# LFR_Array_v2_0.net
KiCad netlist of a schematic drawn in Altium Designer
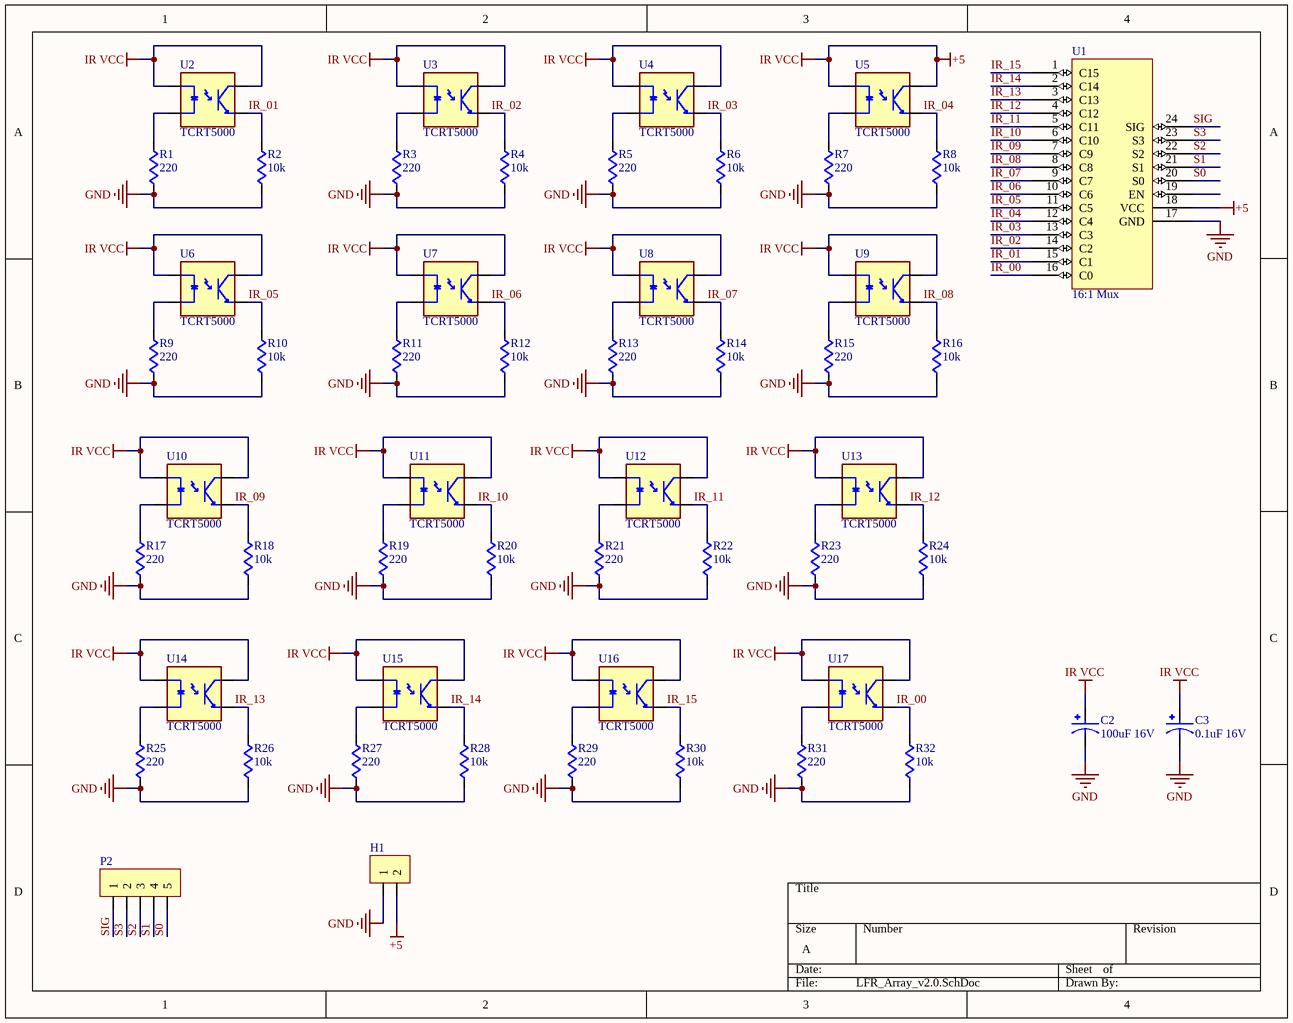
[diagram p0: LFR_Array_v2.0.SchDoc]

(export (version "E")
  (design (tool "Eeschema 10.0.6"))
  (components
    (comp (ref "C2")
      (value "100uF 16V")
      (footprint "100uF  16V")
      (description "CAP ALUM 100uF 16V RADIAL TH")
      (fields (field (name "MP") "EEU-FR1E221B") (field (name "MF") "Panasonic Electronic Components"))
      (libsource (lib "Capacitor TH") (part "100uF 16V"))
    )
    (comp (ref "C3")
      (value "0.1uF 16V")
      (footprint "0.1uF 16V")
      (description "Cap 0.1uF 16VRADIAL TH")
      (fields (field (name "MP") "EEU-FR1E221B") (field (name "MF") "Panasonic Electronic Components"))
      (libsource (lib "Capacitor TH") (part "0.1uF 16V"))
    )
    (comp (ref "H1")
      (value "Header 1x3")
      (footprint "Header 1x2 male CNC")
      (libsource (lib "Pin Header") (part "Header 1x2"))
    )
    (comp (ref "P2")
      (value "Header 1x5")
      (footprint "Header 1x5 male")
      (libsource (lib "Pin Header") (part "Header 1x5"))
    )
    (comp (ref "R1")
      (value "220")
      (footprint "1/4W resistor TH CNC")
      (description "Axial Resistor,reg 220 th")
      (fields (field (name "TOLERANCE") "1%"))
      (libsource (lib "Resistor Generic") (part "reg 220 th"))
    )
    (comp (ref "R2")
      (value "10k")
      (footprint "1/4W resistor TH CNC")
      (description "Axial Resistor,reg 10k th")
      (fields (field (name "TOLERANCE") "1%"))
      (libsource (lib "Resistor Generic") (part "reg 10k th"))
    )
    (comp (ref "R3")
      (value "220")
      (footprint "1/4W resistor TH CNC")
      (description "Axial Resistor,reg 220 th")
      (fields (field (name "TOLERANCE") "1%"))
      (libsource (lib "Resistor Generic") (part "reg 220 th"))
    )
    (comp (ref "R4")
      (value "10k")
      (footprint "1/4W resistor TH CNC")
      (description "Axial Resistor,reg 10k th")
      (fields (field (name "TOLERANCE") "1%"))
      (libsource (lib "Resistor Generic") (part "reg 10k th"))
    )
    (comp (ref "R5")
      (value "220")
      (footprint "1/4W resistor TH CNC")
      (description "Axial Resistor,reg 220 th")
      (fields (field (name "TOLERANCE") "1%"))
      (libsource (lib "Resistor Generic") (part "reg 220 th"))
    )
    (comp (ref "R6")
      (value "10k")
      (footprint "1/4W resistor TH CNC")
      (description "Axial Resistor,reg 10k th")
      (fields (field (name "TOLERANCE") "1%"))
      (libsource (lib "Resistor Generic") (part "reg 10k th"))
    )
    (comp (ref "R7")
      (value "220")
      (footprint "1/4W resistor TH CNC")
      (description "Axial Resistor,reg 220 th")
      (fields (field (name "TOLERANCE") "1%"))
      (libsource (lib "Resistor Generic") (part "reg 220 th"))
    )
    (comp (ref "R8")
      (value "10k")
      (footprint "1/4W resistor TH CNC")
      (description "Axial Resistor,reg 10k th")
      (fields (field (name "TOLERANCE") "1%"))
      (libsource (lib "Resistor Generic") (part "reg 10k th"))
    )
    (comp (ref "R9")
      (value "220")
      (footprint "1/4W resistor TH CNC")
      (description "Axial Resistor,reg 220 th")
      (fields (field (name "TOLERANCE") "1%"))
      (libsource (lib "Resistor Generic") (part "reg 220 th"))
    )
    (comp (ref "R10")
      (value "10k")
      (footprint "1/4W resistor TH CNC")
      (description "Axial Resistor,reg 10k th")
      (fields (field (name "TOLERANCE") "1%"))
      (libsource (lib "Resistor Generic") (part "reg 10k th"))
    )
    (comp (ref "R11")
      (value "220")
      (footprint "1/4W resistor TH CNC")
      (description "Axial Resistor,reg 220 th")
      (fields (field (name "TOLERANCE") "1%"))
      (libsource (lib "Resistor Generic") (part "reg 220 th"))
    )
    (comp (ref "R12")
      (value "10k")
      (footprint "1/4W resistor TH CNC")
      (description "Axial Resistor,reg 10k th")
      (fields (field (name "TOLERANCE") "1%"))
      (libsource (lib "Resistor Generic") (part "reg 10k th"))
    )
    (comp (ref "R13")
      (value "220")
      (footprint "1/4W resistor TH CNC")
      (description "Axial Resistor,reg 220 th")
      (fields (field (name "TOLERANCE") "1%"))
      (libsource (lib "Resistor Generic") (part "reg 220 th"))
    )
    (comp (ref "R14")
      (value "10k")
      (footprint "1/4W resistor TH CNC")
      (description "Axial Resistor,reg 10k th")
      (fields (field (name "TOLERANCE") "1%"))
      (libsource (lib "Resistor Generic") (part "reg 10k th"))
    )
    (comp (ref "R15")
      (value "220")
      (footprint "1/4W resistor TH CNC")
      (description "Axial Resistor,reg 220 th")
      (fields (field (name "TOLERANCE") "1%"))
      (libsource (lib "Resistor Generic") (part "reg 220 th"))
    )
    (comp (ref "R16")
      (value "10k")
      (footprint "1/4W resistor TH CNC")
      (description "Axial Resistor,reg 10k th")
      (fields (field (name "TOLERANCE") "1%"))
      (libsource (lib "Resistor Generic") (part "reg 10k th"))
    )
    (comp (ref "R17")
      (value "220")
      (footprint "1/4W resistor TH CNC")
      (description "Axial Resistor,reg 220 th")
      (fields (field (name "TOLERANCE") "1%"))
      (libsource (lib "Resistor Generic") (part "reg 220 th"))
    )
    (comp (ref "R18")
      (value "10k")
      (footprint "1/4W resistor TH CNC")
      (description "Axial Resistor,reg 10k th")
      (fields (field (name "TOLERANCE") "1%"))
      (libsource (lib "Resistor Generic") (part "reg 10k th"))
    )
    (comp (ref "R19")
      (value "220")
      (footprint "1/4W resistor TH CNC")
      (description "Axial Resistor,reg 220 th")
      (fields (field (name "TOLERANCE") "1%"))
      (libsource (lib "Resistor Generic") (part "reg 220 th"))
    )
    (comp (ref "R20")
      (value "10k")
      (footprint "1/4W resistor TH CNC")
      (description "Axial Resistor,reg 10k th")
      (fields (field (name "TOLERANCE") "1%"))
      (libsource (lib "Resistor Generic") (part "reg 10k th"))
    )
    (comp (ref "R21")
      (value "220")
      (footprint "1/4W resistor TH CNC")
      (description "Axial Resistor,reg 220 th")
      (fields (field (name "TOLERANCE") "1%"))
      (libsource (lib "Resistor Generic") (part "reg 220 th"))
    )
    (comp (ref "R22")
      (value "10k")
      (footprint "1/4W resistor TH CNC")
      (description "Axial Resistor,reg 10k th")
      (fields (field (name "TOLERANCE") "1%"))
      (libsource (lib "Resistor Generic") (part "reg 10k th"))
    )
    (comp (ref "R23")
      (value "220")
      (footprint "1/4W resistor TH CNC")
      (description "Axial Resistor,reg 220 th")
      (fields (field (name "TOLERANCE") "1%"))
      (libsource (lib "Resistor Generic") (part "reg 220 th"))
    )
    (comp (ref "R24")
      (value "10k")
      (footprint "1/4W resistor TH CNC")
      (description "Axial Resistor,reg 10k th")
      (fields (field (name "TOLERANCE") "1%"))
      (libsource (lib "Resistor Generic") (part "reg 10k th"))
    )
    (comp (ref "R25")
      (value "220")
      (footprint "1/4W resistor TH CNC")
      (description "Axial Resistor,reg 220 th")
      (fields (field (name "TOLERANCE") "1%"))
      (libsource (lib "Resistor Generic") (part "reg 220 th"))
    )
    (comp (ref "R26")
      (value "10k")
      (footprint "1/4W resistor TH CNC")
      (description "Axial Resistor,reg 10k th")
      (fields (field (name "TOLERANCE") "1%"))
      (libsource (lib "Resistor Generic") (part "reg 10k th"))
    )
    (comp (ref "R27")
      (value "220")
      (footprint "1/4W resistor TH CNC")
      (description "Axial Resistor,reg 220 th")
      (fields (field (name "TOLERANCE") "1%"))
      (libsource (lib "Resistor Generic") (part "reg 220 th"))
    )
    (comp (ref "R28")
      (value "10k")
      (footprint "1/4W resistor TH CNC")
      (description "Axial Resistor,reg 10k th")
      (fields (field (name "TOLERANCE") "1%"))
      (libsource (lib "Resistor Generic") (part "reg 10k th"))
    )
    (comp (ref "R29")
      (value "220")
      (footprint "1/4W resistor TH CNC")
      (description "Axial Resistor,reg 220 th")
      (fields (field (name "TOLERANCE") "1%"))
      (libsource (lib "Resistor Generic") (part "reg 220 th"))
    )
    (comp (ref "R30")
      (value "10k")
      (footprint "1/4W resistor TH CNC")
      (description "Axial Resistor,reg 10k th")
      (fields (field (name "TOLERANCE") "1%"))
      (libsource (lib "Resistor Generic") (part "reg 10k th"))
    )
    (comp (ref "R31")
      (value "220")
      (footprint "1/4W resistor TH CNC")
      (description "Axial Resistor,reg 220 th")
      (fields (field (name "TOLERANCE") "1%"))
      (libsource (lib "Resistor Generic") (part "reg 220 th"))
    )
    (comp (ref "R32")
      (value "10k")
      (footprint "1/4W resistor TH CNC")
      (description "Axial Resistor,reg 10k th")
      (fields (field (name "TOLERANCE") "1%"))
      (libsource (lib "Resistor Generic") (part "reg 10k th"))
    )
    (comp (ref "U1")
      (value "16:1 Mux")
      (footprint "Mux 16Ch 74HC4067 Module")
      (libsource (lib "Mux 16Ch 74HC4067 Module") (part "Mux 16Ch 74HC4067 Module"))
    )
    (comp (ref "U2")
      (value "TCRT5000")
      (footprint "OPTO_TCRT5000")
      (description "950 nm 60 mA Through Hole Reflective Optical Sensor with Transistor Output")
      (libsource (lib "TCRT5000") (part "TCRT5000"))
    )
    (comp (ref "U3")
      (value "TCRT5000")
      (footprint "OPTO_TCRT5000")
      (description "950 nm 60 mA Through Hole Reflective Optical Sensor with Transistor Output")
      (libsource (lib "TCRT5000") (part "TCRT5000"))
    )
    (comp (ref "U4")
      (value "TCRT5000")
      (footprint "OPTO_TCRT5000")
      (description "950 nm 60 mA Through Hole Reflective Optical Sensor with Transistor Output")
      (libsource (lib "TCRT5000") (part "TCRT5000"))
    )
    (comp (ref "U5")
      (value "TCRT5000")
      (footprint "OPTO_TCRT5000")
      (description "950 nm 60 mA Through Hole Reflective Optical Sensor with Transistor Output")
      (libsource (lib "TCRT5000") (part "TCRT5000"))
    )
    (comp (ref "U6")
      (value "TCRT5000")
      (footprint "OPTO_TCRT5000")
      (description "950 nm 60 mA Through Hole Reflective Optical Sensor with Transistor Output")
      (libsource (lib "TCRT5000") (part "TCRT5000"))
    )
    (comp (ref "U7")
      (value "TCRT5000")
      (footprint "OPTO_TCRT5000")
      (description "950 nm 60 mA Through Hole Reflective Optical Sensor with Transistor Output")
      (libsource (lib "TCRT5000") (part "TCRT5000"))
    )
    (comp (ref "U8")
      (value "TCRT5000")
      (footprint "OPTO_TCRT5000")
      (description "950 nm 60 mA Through Hole Reflective Optical Sensor with Transistor Output")
      (libsource (lib "TCRT5000") (part "TCRT5000"))
    )
    (comp (ref "U9")
      (value "TCRT5000")
      (footprint "OPTO_TCRT5000")
      (description "950 nm 60 mA Through Hole Reflective Optical Sensor with Transistor Output")
      (libsource (lib "TCRT5000") (part "TCRT5000"))
    )
    (comp (ref "U10")
      (value "TCRT5000")
      (footprint "OPTO_TCRT5000")
      (description "950 nm 60 mA Through Hole Reflective Optical Sensor with Transistor Output")
      (libsource (lib "TCRT5000") (part "TCRT5000"))
    )
    (comp (ref "U11")
      (value "TCRT5000")
      (footprint "OPTO_TCRT5000")
      (description "950 nm 60 mA Through Hole Reflective Optical Sensor with Transistor Output")
      (libsource (lib "TCRT5000") (part "TCRT5000"))
    )
    (comp (ref "U12")
      (value "TCRT5000")
      (footprint "OPTO_TCRT5000")
      (description "950 nm 60 mA Through Hole Reflective Optical Sensor with Transistor Output")
      (libsource (lib "TCRT5000") (part "TCRT5000"))
    )
    (comp (ref "U13")
      (value "TCRT5000")
      (footprint "OPTO_TCRT5000")
      (description "950 nm 60 mA Through Hole Reflective Optical Sensor with Transistor Output")
      (libsource (lib "TCRT5000") (part "TCRT5000"))
    )
    (comp (ref "U14")
      (value "TCRT5000")
      (footprint "OPTO_TCRT5000")
      (description "950 nm 60 mA Through Hole Reflective Optical Sensor with Transistor Output")
      (libsource (lib "TCRT5000") (part "TCRT5000"))
    )
    (comp (ref "U15")
      (value "TCRT5000")
      (footprint "OPTO_TCRT5000")
      (description "950 nm 60 mA Through Hole Reflective Optical Sensor with Transistor Output")
      (libsource (lib "TCRT5000") (part "TCRT5000"))
    )
    (comp (ref "U16")
      (value "TCRT5000")
      (footprint "OPTO_TCRT5000")
      (description "950 nm 60 mA Through Hole Reflective Optical Sensor with Transistor Output")
      (libsource (lib "TCRT5000") (part "TCRT5000"))
    )
    (comp (ref "U17")
      (value "TCRT5000")
      (footprint "OPTO_TCRT5000")
      (description "950 nm 60 mA Through Hole Reflective Optical Sensor with Transistor Output")
      (libsource (lib "TCRT5000") (part "TCRT5000"))
    )
  )
  (nets
    (net (code "1") (name "+5") (class "Default")
      (node (ref "C2") (pin "P") (pinfunction "P_P") (pintype "passive"))
      (node (ref "C3") (pin "P") (pinfunction "P_P") (pintype "passive"))
      (node (ref "H1") (pin "2") (pinfunction "2_2") (pintype "passive"))
      (node (ref "U1") (pin "18") (pinfunction "VCC_18") (pintype "power_in"))
      (node (ref "U10") (pin "A") (pinfunction "A_A") (pintype "passive"))
      (node (ref "U10") (pin "COLL") (pinfunction "COLL_COLL") (pintype "passive"))
      (node (ref "U11") (pin "A") (pinfunction "A_A") (pintype "passive"))
      (node (ref "U11") (pin "COLL") (pinfunction "COLL_COLL") (pintype "passive"))
      (node (ref "U12") (pin "A") (pinfunction "A_A") (pintype "passive"))
      (node (ref "U12") (pin "COLL") (pinfunction "COLL_COLL") (pintype "passive"))
      (node (ref "U13") (pin "A") (pinfunction "A_A") (pintype "passive"))
      (node (ref "U13") (pin "COLL") (pinfunction "COLL_COLL") (pintype "passive"))
      (node (ref "U14") (pin "A") (pinfunction "A_A") (pintype "passive"))
      (node (ref "U14") (pin "COLL") (pinfunction "COLL_COLL") (pintype "passive"))
      (node (ref "U15") (pin "A") (pinfunction "A_A") (pintype "passive"))
      (node (ref "U15") (pin "COLL") (pinfunction "COLL_COLL") (pintype "passive"))
      (node (ref "U16") (pin "A") (pinfunction "A_A") (pintype "passive"))
      (node (ref "U16") (pin "COLL") (pinfunction "COLL_COLL") (pintype "passive"))
      (node (ref "U17") (pin "A") (pinfunction "A_A") (pintype "passive"))
      (node (ref "U17") (pin "COLL") (pinfunction "COLL_COLL") (pintype "passive"))
      (node (ref "U2") (pin "A") (pinfunction "A_A") (pintype "passive"))
      (node (ref "U2") (pin "COLL") (pinfunction "COLL_COLL") (pintype "passive"))
      (node (ref "U3") (pin "A") (pinfunction "A_A") (pintype "passive"))
      (node (ref "U3") (pin "COLL") (pinfunction "COLL_COLL") (pintype "passive"))
      (node (ref "U4") (pin "A") (pinfunction "A_A") (pintype "passive"))
      (node (ref "U4") (pin "COLL") (pinfunction "COLL_COLL") (pintype "passive"))
      (node (ref "U5") (pin "A") (pinfunction "A_A") (pintype "passive"))
      (node (ref "U5") (pin "COLL") (pinfunction "COLL_COLL") (pintype "passive"))
      (node (ref "U6") (pin "A") (pinfunction "A_A") (pintype "passive"))
      (node (ref "U6") (pin "COLL") (pinfunction "COLL_COLL") (pintype "passive"))
      (node (ref "U7") (pin "A") (pinfunction "A_A") (pintype "passive"))
      (node (ref "U7") (pin "COLL") (pinfunction "COLL_COLL") (pintype "passive"))
      (node (ref "U8") (pin "A") (pinfunction "A_A") (pintype "passive"))
      (node (ref "U8") (pin "COLL") (pinfunction "COLL_COLL") (pintype "passive"))
      (node (ref "U9") (pin "A") (pinfunction "A_A") (pintype "passive"))
      (node (ref "U9") (pin "COLL") (pinfunction "COLL_COLL") (pintype "passive"))
    )
    (net (code "2") (name "/IR_00") (class "Default")
      (node (ref "R32") (pin "2") (pinfunction "2_2") (pintype "passive"))
      (node (ref "U1") (pin "16") (pinfunction "C0_16") (pintype "bidirectional"))
      (node (ref "U17") (pin "E") (pinfunction "E_E") (pintype "passive"))
    )
    (net (code "3") (name "/IR_01") (class "Default")
      (node (ref "R2") (pin "2") (pinfunction "2_2") (pintype "passive"))
      (node (ref "U1") (pin "15") (pinfunction "C1_15") (pintype "bidirectional"))
      (node (ref "U2") (pin "E") (pinfunction "E_E") (pintype "passive"))
    )
    (net (code "4") (name "/IR_02") (class "Default")
      (node (ref "R4") (pin "2") (pinfunction "2_2") (pintype "passive"))
      (node (ref "U1") (pin "14") (pinfunction "C2_14") (pintype "bidirectional"))
      (node (ref "U3") (pin "E") (pinfunction "E_E") (pintype "passive"))
    )
    (net (code "5") (name "/IR_03") (class "Default")
      (node (ref "R6") (pin "2") (pinfunction "2_2") (pintype "passive"))
      (node (ref "U1") (pin "13") (pinfunction "C3_13") (pintype "bidirectional"))
      (node (ref "U4") (pin "E") (pinfunction "E_E") (pintype "passive"))
    )
    (net (code "6") (name "/IR_04") (class "Default")
      (node (ref "R8") (pin "2") (pinfunction "2_2") (pintype "passive"))
      (node (ref "U1") (pin "12") (pinfunction "C4_12") (pintype "bidirectional"))
      (node (ref "U5") (pin "E") (pinfunction "E_E") (pintype "passive"))
    )
    (net (code "7") (name "/IR_05") (class "Default")
      (node (ref "R10") (pin "2") (pinfunction "2_2") (pintype "passive"))
      (node (ref "U1") (pin "11") (pinfunction "C5_11") (pintype "bidirectional"))
      (node (ref "U6") (pin "E") (pinfunction "E_E") (pintype "passive"))
    )
    (net (code "8") (name "/IR_06") (class "Default")
      (node (ref "R12") (pin "2") (pinfunction "2_2") (pintype "passive"))
      (node (ref "U1") (pin "10") (pinfunction "C6_10") (pintype "bidirectional"))
      (node (ref "U7") (pin "E") (pinfunction "E_E") (pintype "passive"))
    )
    (net (code "9") (name "/IR_07") (class "Default")
      (node (ref "R14") (pin "2") (pinfunction "2_2") (pintype "passive"))
      (node (ref "U1") (pin "9") (pinfunction "C7_9") (pintype "bidirectional"))
      (node (ref "U8") (pin "E") (pinfunction "E_E") (pintype "passive"))
    )
    (net (code "10") (name "/IR_08") (class "Default")
      (node (ref "R16") (pin "2") (pinfunction "2_2") (pintype "passive"))
      (node (ref "U1") (pin "8") (pinfunction "C8_8") (pintype "bidirectional"))
      (node (ref "U9") (pin "E") (pinfunction "E_E") (pintype "passive"))
    )
    (net (code "11") (name "/IR_09") (class "Default")
      (node (ref "R18") (pin "2") (pinfunction "2_2") (pintype "passive"))
      (node (ref "U1") (pin "7") (pinfunction "C9_7") (pintype "bidirectional"))
      (node (ref "U10") (pin "E") (pinfunction "E_E") (pintype "passive"))
    )
    (net (code "12") (name "/IR_10") (class "Default")
      (node (ref "R20") (pin "2") (pinfunction "2_2") (pintype "passive"))
      (node (ref "U1") (pin "6") (pinfunction "C10_6") (pintype "bidirectional"))
      (node (ref "U11") (pin "E") (pinfunction "E_E") (pintype "passive"))
    )
    (net (code "13") (name "/IR_11") (class "Default")
      (node (ref "R22") (pin "2") (pinfunction "2_2") (pintype "passive"))
      (node (ref "U1") (pin "5") (pinfunction "C11_5") (pintype "bidirectional"))
      (node (ref "U12") (pin "E") (pinfunction "E_E") (pintype "passive"))
    )
    (net (code "14") (name "/IR_12") (class "Default")
      (node (ref "R24") (pin "2") (pinfunction "2_2") (pintype "passive"))
      (node (ref "U1") (pin "4") (pinfunction "C12_4") (pintype "bidirectional"))
      (node (ref "U13") (pin "E") (pinfunction "E_E") (pintype "passive"))
    )
    (net (code "15") (name "/IR_13") (class "Default")
      (node (ref "R26") (pin "2") (pinfunction "2_2") (pintype "passive"))
      (node (ref "U1") (pin "3") (pinfunction "C13_3") (pintype "bidirectional"))
      (node (ref "U14") (pin "E") (pinfunction "E_E") (pintype "passive"))
    )
    (net (code "16") (name "/IR_14") (class "Default")
      (node (ref "R28") (pin "2") (pinfunction "2_2") (pintype "passive"))
      (node (ref "U1") (pin "2") (pinfunction "C14_2") (pintype "bidirectional"))
      (node (ref "U15") (pin "E") (pinfunction "E_E") (pintype "passive"))
    )
    (net (code "17") (name "/IR_15") (class "Default")
      (node (ref "R30") (pin "2") (pinfunction "2_2") (pintype "passive"))
      (node (ref "U1") (pin "1") (pinfunction "C15_1") (pintype "bidirectional"))
      (node (ref "U16") (pin "E") (pinfunction "E_E") (pintype "passive"))
    )
    (net (code "18") (name "/S0") (class "Default")
      (node (ref "P2") (pin "5") (pinfunction "5_5") (pintype "passive"))
      (node (ref "U1") (pin "20") (pinfunction "S0_20") (pintype "bidirectional"))
    )
    (net (code "19") (name "/S1") (class "Default")
      (node (ref "P2") (pin "4") (pinfunction "4_4") (pintype "passive"))
      (node (ref "U1") (pin "21") (pinfunction "S1_21") (pintype "bidirectional"))
    )
    (net (code "20") (name "/S2") (class "Default")
      (node (ref "P2") (pin "3") (pinfunction "3_3") (pintype "passive"))
      (node (ref "U1") (pin "22") (pinfunction "S2_22") (pintype "bidirectional"))
    )
    (net (code "21") (name "/S3") (class "Default")
      (node (ref "P2") (pin "2") (pinfunction "2_2") (pintype "passive"))
      (node (ref "U1") (pin "23") (pinfunction "S3_23") (pintype "bidirectional"))
    )
    (net (code "22") (name "/SIG") (class "Default")
      (node (ref "P2") (pin "1") (pinfunction "1_1") (pintype "passive"))
      (node (ref "U1") (pin "24") (pinfunction "SIG_24") (pintype "bidirectional"))
    )
    (net (code "23") (name "GND") (class "Default")
      (node (ref "C2") (pin "N") (pinfunction "N_N") (pintype "passive"))
      (node (ref "C3") (pin "N") (pinfunction "N_N") (pintype "passive"))
      (node (ref "H1") (pin "1") (pinfunction "1_1") (pintype "passive"))
      (node (ref "R1") (pin "1") (pinfunction "1_1") (pintype "passive"))
      (node (ref "R10") (pin "1") (pinfunction "1_1") (pintype "passive"))
      (node (ref "R11") (pin "1") (pinfunction "1_1") (pintype "passive"))
      (node (ref "R12") (pin "1") (pinfunction "1_1") (pintype "passive"))
      (node (ref "R13") (pin "1") (pinfunction "1_1") (pintype "passive"))
      (node (ref "R14") (pin "1") (pinfunction "1_1") (pintype "passive"))
      (node (ref "R15") (pin "1") (pinfunction "1_1") (pintype "passive"))
      (node (ref "R16") (pin "1") (pinfunction "1_1") (pintype "passive"))
      (node (ref "R17") (pin "1") (pinfunction "1_1") (pintype "passive"))
      (node (ref "R18") (pin "1") (pinfunction "1_1") (pintype "passive"))
      (node (ref "R19") (pin "1") (pinfunction "1_1") (pintype "passive"))
      (node (ref "R2") (pin "1") (pinfunction "1_1") (pintype "passive"))
      (node (ref "R20") (pin "1") (pinfunction "1_1") (pintype "passive"))
      (node (ref "R21") (pin "1") (pinfunction "1_1") (pintype "passive"))
      (node (ref "R22") (pin "1") (pinfunction "1_1") (pintype "passive"))
      (node (ref "R23") (pin "1") (pinfunction "1_1") (pintype "passive"))
      (node (ref "R24") (pin "1") (pinfunction "1_1") (pintype "passive"))
      (node (ref "R25") (pin "1") (pinfunction "1_1") (pintype "passive"))
      (node (ref "R26") (pin "1") (pinfunction "1_1") (pintype "passive"))
      (node (ref "R27") (pin "1") (pinfunction "1_1") (pintype "passive"))
      (node (ref "R28") (pin "1") (pinfunction "1_1") (pintype "passive"))
      (node (ref "R29") (pin "1") (pinfunction "1_1") (pintype "passive"))
      (node (ref "R3") (pin "1") (pinfunction "1_1") (pintype "passive"))
      (node (ref "R30") (pin "1") (pinfunction "1_1") (pintype "passive"))
      (node (ref "R31") (pin "1") (pinfunction "1_1") (pintype "passive"))
      (node (ref "R32") (pin "1") (pinfunction "1_1") (pintype "passive"))
      (node (ref "R4") (pin "1") (pinfunction "1_1") (pintype "passive"))
      (node (ref "R5") (pin "1") (pinfunction "1_1") (pintype "passive"))
      (node (ref "R6") (pin "1") (pinfunction "1_1") (pintype "passive"))
      (node (ref "R7") (pin "1") (pinfunction "1_1") (pintype "passive"))
      (node (ref "R8") (pin "1") (pinfunction "1_1") (pintype "passive"))
      (node (ref "R9") (pin "1") (pinfunction "1_1") (pintype "passive"))
      (node (ref "U1") (pin "17") (pinfunction "GND_17") (pintype "power_in"))
    )
    (net (code "24") (name "Net-(R1-Pad2)") (class "Default")
      (node (ref "R1") (pin "2") (pinfunction "2_2") (pintype "passive"))
      (node (ref "U2") (pin "CATH") (pinfunction "CATH_CATH") (pintype "passive"))
    )
    (net (code "25") (name "Net-(R3-Pad2)") (class "Default")
      (node (ref "R3") (pin "2") (pinfunction "2_2") (pintype "passive"))
      (node (ref "U3") (pin "CATH") (pinfunction "CATH_CATH") (pintype "passive"))
    )
    (net (code "26") (name "Net-(R5-Pad2)") (class "Default")
      (node (ref "R5") (pin "2") (pinfunction "2_2") (pintype "passive"))
      (node (ref "U4") (pin "CATH") (pinfunction "CATH_CATH") (pintype "passive"))
    )
    (net (code "27") (name "Net-(R7-Pad2)") (class "Default")
      (node (ref "R7") (pin "2") (pinfunction "2_2") (pintype "passive"))
      (node (ref "U5") (pin "CATH") (pinfunction "CATH_CATH") (pintype "passive"))
    )
    (net (code "28") (name "Net-(R9-Pad2)") (class "Default")
      (node (ref "R9") (pin "2") (pinfunction "2_2") (pintype "passive"))
      (node (ref "U6") (pin "CATH") (pinfunction "CATH_CATH") (pintype "passive"))
    )
    (net (code "29") (name "Net-(R11-Pad2)") (class "Default")
      (node (ref "R11") (pin "2") (pinfunction "2_2") (pintype "passive"))
      (node (ref "U7") (pin "CATH") (pinfunction "CATH_CATH") (pintype "passive"))
    )
    (net (code "30") (name "Net-(R13-Pad2)") (class "Default")
      (node (ref "R13") (pin "2") (pinfunction "2_2") (pintype "passive"))
      (node (ref "U8") (pin "CATH") (pinfunction "CATH_CATH") (pintype "passive"))
    )
    (net (code "31") (name "Net-(R15-Pad2)") (class "Default")
      (node (ref "R15") (pin "2") (pinfunction "2_2") (pintype "passive"))
      (node (ref "U9") (pin "CATH") (pinfunction "CATH_CATH") (pintype "passive"))
    )
    (net (code "32") (name "Net-(R17-Pad2)") (class "Default")
      (node (ref "R17") (pin "2") (pinfunction "2_2") (pintype "passive"))
      (node (ref "U10") (pin "CATH") (pinfunction "CATH_CATH") (pintype "passive"))
    )
    (net (code "33") (name "Net-(R19-Pad2)") (class "Default")
      (node (ref "R19") (pin "2") (pinfunction "2_2") (pintype "passive"))
      (node (ref "U11") (pin "CATH") (pinfunction "CATH_CATH") (pintype "passive"))
    )
    (net (code "34") (name "Net-(R21-Pad2)") (class "Default")
      (node (ref "R21") (pin "2") (pinfunction "2_2") (pintype "passive"))
      (node (ref "U12") (pin "CATH") (pinfunction "CATH_CATH") (pintype "passive"))
    )
    (net (code "35") (name "Net-(R23-Pad2)") (class "Default")
      (node (ref "R23") (pin "2") (pinfunction "2_2") (pintype "passive"))
      (node (ref "U13") (pin "CATH") (pinfunction "CATH_CATH") (pintype "passive"))
    )
    (net (code "36") (name "Net-(R25-Pad2)") (class "Default")
      (node (ref "R25") (pin "2") (pinfunction "2_2") (pintype "passive"))
      (node (ref "U14") (pin "CATH") (pinfunction "CATH_CATH") (pintype "passive"))
    )
    (net (code "37") (name "Net-(R27-Pad2)") (class "Default")
      (node (ref "R27") (pin "2") (pinfunction "2_2") (pintype "passive"))
      (node (ref "U15") (pin "CATH") (pinfunction "CATH_CATH") (pintype "passive"))
    )
    (net (code "38") (name "Net-(R29-Pad2)") (class "Default")
      (node (ref "R29") (pin "2") (pinfunction "2_2") (pintype "passive"))
      (node (ref "U16") (pin "CATH") (pinfunction "CATH_CATH") (pintype "passive"))
    )
    (net (code "39") (name "Net-(R31-Pad2)") (class "Default")
      (node (ref "R31") (pin "2") (pinfunction "2_2") (pintype "passive"))
      (node (ref "U17") (pin "CATH") (pinfunction "CATH_CATH") (pintype "passive"))
    )
    (net (code "40") (name "unconnected-(U1-EN-Pad19)") (class "Default")
      (node (ref "U1") (pin "19") (pinfunction "EN_19") (pintype "bidirectional"))
    )
  )
)
